# nano.net
KiCad netlist of a schematic drawn in EAGLE
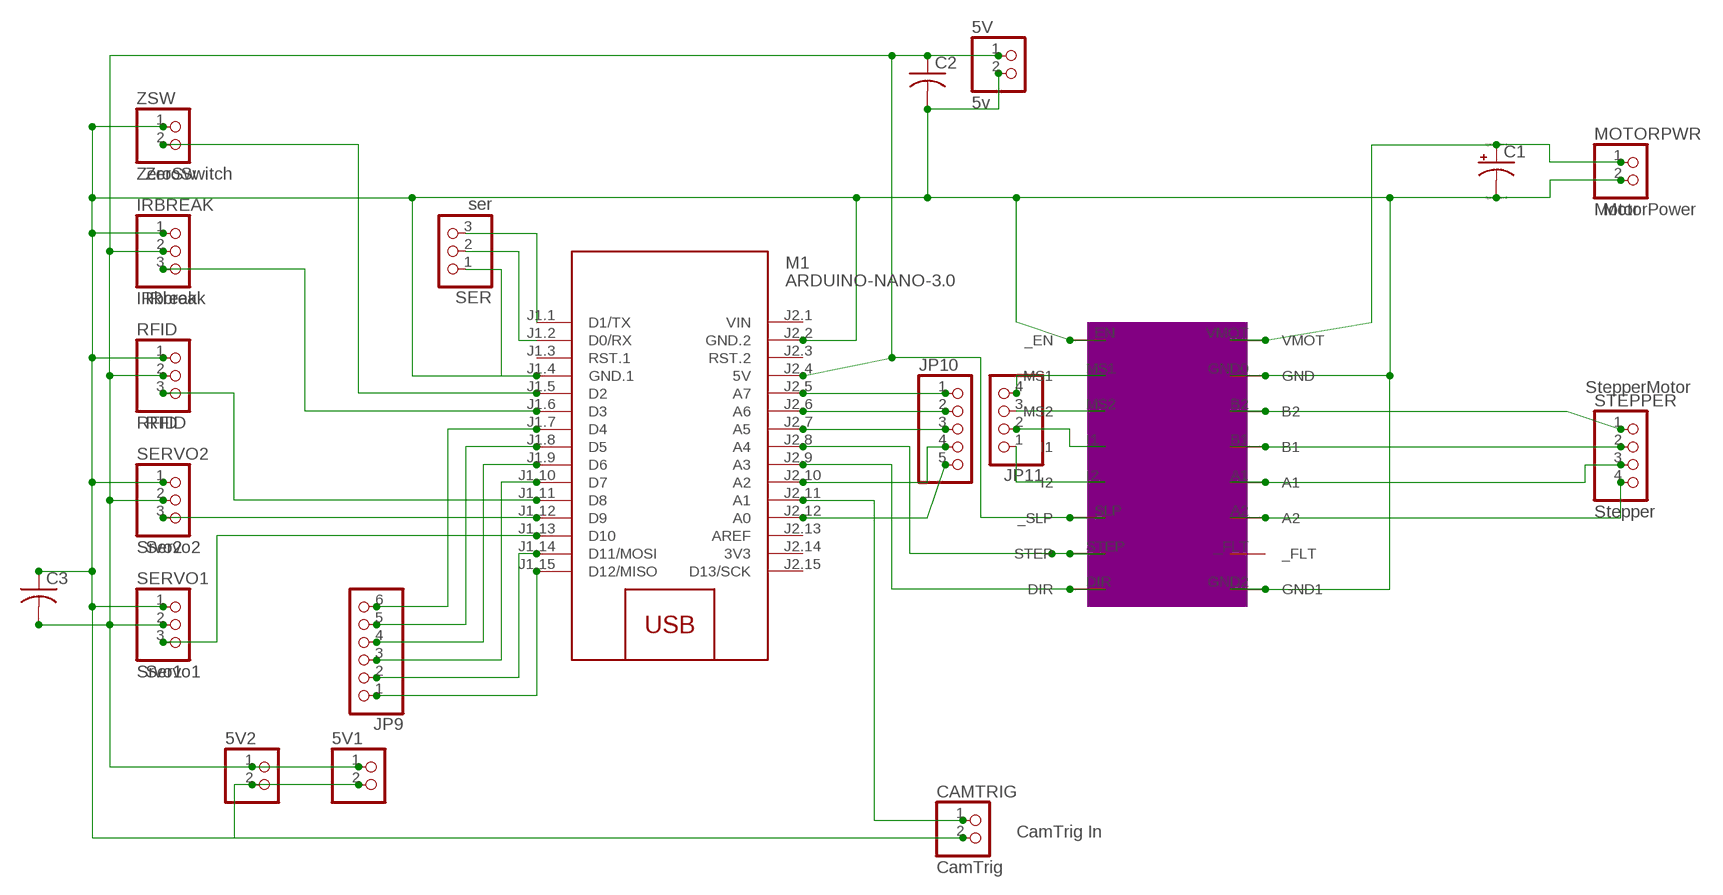
[diagram p0: schematic, sheet 1]

(export (version "E")
  (design (tool "Eeschema 10.0.6"))
  (components
    (comp (ref "5V")
      (value "5v")
      (footprint "eagle-import:1X02")
      (libsource (lib "eagle-import") (part "PINHD-1X2"))
    )
    (comp (ref "5V1")
      (value "PINHD-1X2")
      (footprint "eagle-import:1X02")
      (libsource (lib "eagle-import") (part "PINHD-1X2"))
    )
    (comp (ref "5V2")
      (value "PINHD-1X2")
      (footprint "eagle-import:1X02")
      (libsource (lib "eagle-import") (part "PINHD-1X2"))
    )
    (comp (ref "C1")
      (value "CPOL-USE5-5")
      (footprint "eagle-import:E5-5")
      (libsource (lib "eagle-import") (part "CPOL-USE5-5"))
    )
    (comp (ref "C2")
      (value "C-USC0805")
      (footprint "eagle-import:C0805")
      (libsource (lib "eagle-import") (part "C-USC0805"))
    )
    (comp (ref "C3")
      (value "C-USC0805")
      (footprint "eagle-import:C0805")
      (libsource (lib "eagle-import") (part "C-USC0805"))
    )
    (comp (ref "CAMTRIG")
      (value "CamTrig")
      (footprint "eagle-import:1X02")
      (libsource (lib "eagle-import") (part "PINHD-1X2"))
    )
    (comp (ref "IRBREAK")
      (value "IRbreak")
      (footprint "eagle-import:1X03")
      (libsource (lib "eagle-import") (part "PINHD-1X3"))
    )
    (comp (ref "JP9")
      (value "PINHD-1X6")
      (footprint "eagle-import:1X06")
      (libsource (lib "eagle-import") (part "PINHD-1X6"))
    )
    (comp (ref "JP10")
      (value "PINHD-1X5")
      (footprint "eagle-import:1X05")
      (libsource (lib "eagle-import") (part "PINHD-1X5"))
    )
    (comp (ref "JP11")
      (value "PINHD-1X4")
      (footprint "eagle-import:1X04")
      (libsource (lib "eagle-import") (part "PINHD-1X4"))
    )
    (comp (ref "M1")
      (value "ARDUINO-NANO-3.0")
      (footprint "eagle-import:ARDUINO-NANO-3.0")
      (libsource (lib "eagle-import") (part "ARDUINO-NANO-3.0"))
    )
    (comp (ref "MOTORPWR")
      (value "Motor")
      (footprint "eagle-import:1X02")
      (libsource (lib "eagle-import") (part "PINHD-1X2"))
    )
    (comp (ref "RFID")
      (value "RFID")
      (footprint "eagle-import:1X03")
      (libsource (lib "eagle-import") (part "PINHD-1X3"))
    )
    (comp (ref "SER")
      (value "ser")
      (footprint "eagle-import:1X03")
      (libsource (lib "eagle-import") (part "PINHD-1X3"))
    )
    (comp (ref "SERVO1")
      (value "Srvo1")
      (footprint "eagle-import:1X03")
      (libsource (lib "eagle-import") (part "PINHD-1X3"))
    )
    (comp (ref "SERVO2")
      (value "Srvo2")
      (footprint "eagle-import:1X03")
      (libsource (lib "eagle-import") (part "PINHD-1X3"))
    )
    (comp (ref "STEPPER")
      (value "Stepper")
      (footprint "eagle-import:1X04")
      (libsource (lib "eagle-import") (part "PINHD-1X4"))
    )
    (comp (ref "U$1")
      (value "MP6500")
      (footprint "eagle-import:MP6500")
      (libsource (lib "eagle-import") (part "MP6500"))
    )
    (comp (ref "ZSW")
      (value "ZeroSw")
      (footprint "eagle-import:1X02")
      (libsource (lib "eagle-import") (part "PINHD-1X2"))
    )
  )
  (nets
    (net (code "1") (name "/3V3") (class "Default")
      (node (ref "M1") (pin "J2.14") (pinfunction "3V3_J2.14") (pintype "power_in"))
    )
    (net (code "2") (name "/VIN") (class "Default")
      (node (ref "M1") (pin "J2.1") (pinfunction "VIN_J2.1") (pintype "power_in"))
    )
    (net (code "3") (name "Net-(C1-Pad+)") (class "Default")
      (node (ref "C1") (pin "+") (pinfunction "+_+") (pintype "passive"))
      (node (ref "MOTORPWR") (pin "1") (pinfunction "1_1") (pintype "passive"))
      (node (ref "U$1") (pin "VMOT") (pinfunction "VMOT_VMOT") (pintype "bidirectional"))
    )
    (net (code "4") (name "Net-(JP11-Pad1)") (class "Default")
      (node (ref "JP11") (pin "1") (pinfunction "1_1") (pintype "passive"))
      (node (ref "U$1") (pin "I2") (pinfunction "I2_I2") (pintype "bidirectional"))
    )
    (net (code "5") (name "Net-(JP11-Pad2)") (class "Default")
      (node (ref "JP11") (pin "2") (pinfunction "2_2") (pintype "passive"))
      (node (ref "U$1") (pin "I1") (pinfunction "I1_I1") (pintype "bidirectional"))
    )
    (net (code "6") (name "Net-(JP11-Pad3)") (class "Default")
      (node (ref "JP11") (pin "3") (pinfunction "3_3") (pintype "passive"))
      (node (ref "U$1") (pin "MS2") (pinfunction "MS2_MS2") (pintype "bidirectional"))
    )
    (net (code "7") (name "Net-(JP11-Pad4)") (class "Default")
      (node (ref "JP11") (pin "4") (pinfunction "4_4") (pintype "passive"))
      (node (ref "U$1") (pin "MS1") (pinfunction "MS1_MS1") (pintype "bidirectional"))
    )
    (net (code "8") (name "Net-(M1-5V)") (class "Default")
      (node (ref "5V") (pin "1") (pinfunction "1_1") (pintype "passive"))
      (node (ref "5V1") (pin "1") (pinfunction "1_1") (pintype "passive"))
      (node (ref "5V2") (pin "1") (pinfunction "1_1") (pintype "passive"))
      (node (ref "C2") (pin "1") (pinfunction "1_1") (pintype "passive"))
      (node (ref "C3") (pin "2") (pinfunction "2_2") (pintype "passive"))
      (node (ref "IRBREAK") (pin "2") (pinfunction "2_2") (pintype "passive"))
      (node (ref "M1") (pin "J2.4") (pinfunction "5V_J2.4") (pintype "power_in"))
      (node (ref "RFID") (pin "2") (pinfunction "2_2") (pintype "passive"))
      (node (ref "SERVO1") (pin "2") (pinfunction "2_2") (pintype "passive"))
      (node (ref "SERVO2") (pin "2") (pinfunction "2_2") (pintype "passive"))
      (node (ref "U$1") (pin "_SLP") (pinfunction "_SLP__SLP") (pintype "bidirectional"))
    )
    (net (code "9") (name "Net-(M1-A0)") (class "Default")
      (node (ref "JP10") (pin "5") (pinfunction "5_5") (pintype "passive"))
      (node (ref "M1") (pin "J2.12") (pinfunction "A0_J2.12") (pintype "bidirectional"))
    )
    (net (code "10") (name "Net-(M1-A1)") (class "Default")
      (node (ref "CAMTRIG") (pin "1") (pinfunction "1_1") (pintype "passive"))
      (node (ref "M1") (pin "J2.11") (pinfunction "A1_J2.11") (pintype "bidirectional"))
    )
    (net (code "11") (name "Net-(M1-A2)") (class "Default")
      (node (ref "JP10") (pin "4") (pinfunction "4_4") (pintype "passive"))
      (node (ref "M1") (pin "J2.10") (pinfunction "A2_J2.10") (pintype "bidirectional"))
    )
    (net (code "12") (name "Net-(M1-A3)") (class "Default")
      (node (ref "M1") (pin "J2.9") (pinfunction "A3_J2.9") (pintype "bidirectional"))
      (node (ref "U$1") (pin "DIR") (pinfunction "DIR_DIR") (pintype "bidirectional"))
    )
    (net (code "13") (name "Net-(M1-A4)") (class "Default")
      (node (ref "M1") (pin "J2.8") (pinfunction "A4_J2.8") (pintype "bidirectional"))
      (node (ref "U$1") (pin "STEP") (pinfunction "STEP_STEP") (pintype "bidirectional"))
    )
    (net (code "14") (name "Net-(M1-A5)") (class "Default")
      (node (ref "JP10") (pin "3") (pinfunction "3_3") (pintype "passive"))
      (node (ref "M1") (pin "J2.7") (pinfunction "A5_J2.7") (pintype "bidirectional"))
    )
    (net (code "15") (name "Net-(M1-A6)") (class "Default")
      (node (ref "JP10") (pin "2") (pinfunction "2_2") (pintype "passive"))
      (node (ref "M1") (pin "J2.6") (pinfunction "A6_J2.6") (pintype "bidirectional"))
    )
    (net (code "16") (name "Net-(M1-A7)") (class "Default")
      (node (ref "JP10") (pin "1") (pinfunction "1_1") (pintype "passive"))
      (node (ref "M1") (pin "J2.5") (pinfunction "A7_J2.5") (pintype "bidirectional"))
    )
    (net (code "17") (name "Net-(M1-D0{slash}RX)") (class "Default")
      (node (ref "M1") (pin "J1.2") (pinfunction "D0/RX_J1.2") (pintype "bidirectional"))
      (node (ref "SER") (pin "2") (pinfunction "2_2") (pintype "passive"))
    )
    (net (code "18") (name "Net-(M1-D1{slash}TX)") (class "Default")
      (node (ref "M1") (pin "J1.1") (pinfunction "D1/TX_J1.1") (pintype "bidirectional"))
      (node (ref "SER") (pin "3") (pinfunction "3_3") (pintype "passive"))
    )
    (net (code "19") (name "Net-(M1-D2)") (class "Default")
      (node (ref "M1") (pin "J1.5") (pinfunction "D2_J1.5") (pintype "bidirectional"))
      (node (ref "ZSW") (pin "2") (pinfunction "2_2") (pintype "passive"))
    )
    (net (code "20") (name "Net-(M1-D3)") (class "Default")
      (node (ref "IRBREAK") (pin "3") (pinfunction "3_3") (pintype "passive"))
      (node (ref "M1") (pin "J1.6") (pinfunction "D3_J1.6") (pintype "bidirectional"))
    )
    (net (code "21") (name "Net-(M1-D4)") (class "Default")
      (node (ref "JP9") (pin "6") (pinfunction "6_6") (pintype "passive"))
      (node (ref "M1") (pin "J1.7") (pinfunction "D4_J1.7") (pintype "bidirectional"))
    )
    (net (code "22") (name "Net-(M1-D5)") (class "Default")
      (node (ref "JP9") (pin "5") (pinfunction "5_5") (pintype "passive"))
      (node (ref "M1") (pin "J1.8") (pinfunction "D5_J1.8") (pintype "bidirectional"))
    )
    (net (code "23") (name "Net-(M1-D6)") (class "Default")
      (node (ref "JP9") (pin "4") (pinfunction "4_4") (pintype "passive"))
      (node (ref "M1") (pin "J1.9") (pinfunction "D6_J1.9") (pintype "bidirectional"))
    )
    (net (code "24") (name "Net-(M1-D7)") (class "Default")
      (node (ref "JP9") (pin "3") (pinfunction "3_3") (pintype "passive"))
      (node (ref "M1") (pin "J1.10") (pinfunction "D7_J1.10") (pintype "bidirectional"))
    )
    (net (code "25") (name "Net-(M1-D8)") (class "Default")
      (node (ref "M1") (pin "J1.11") (pinfunction "D8_J1.11") (pintype "bidirectional"))
      (node (ref "RFID") (pin "3") (pinfunction "3_3") (pintype "passive"))
    )
    (net (code "26") (name "Net-(M1-D9)") (class "Default")
      (node (ref "M1") (pin "J1.12") (pinfunction "D9_J1.12") (pintype "bidirectional"))
      (node (ref "SERVO2") (pin "3") (pinfunction "3_3") (pintype "passive"))
    )
    (net (code "27") (name "Net-(M1-D10)") (class "Default")
      (node (ref "M1") (pin "J1.13") (pinfunction "D10_J1.13") (pintype "bidirectional"))
      (node (ref "SERVO1") (pin "3") (pinfunction "3_3") (pintype "passive"))
    )
    (net (code "28") (name "Net-(M1-D11{slash}MOSI)") (class "Default")
      (node (ref "JP9") (pin "2") (pinfunction "2_2") (pintype "passive"))
      (node (ref "M1") (pin "J1.14") (pinfunction "D11/MOSI_J1.14") (pintype "bidirectional"))
    )
    (net (code "29") (name "Net-(M1-D12{slash}MISO)") (class "Default")
      (node (ref "JP9") (pin "1") (pinfunction "1_1") (pintype "passive"))
      (node (ref "M1") (pin "J1.15") (pinfunction "D12/MISO_J1.15") (pintype "bidirectional"))
    )
    (net (code "30") (name "Net-(M1-GND.1)") (class "Default")
      (node (ref "5V") (pin "2") (pinfunction "2_2") (pintype "passive"))
      (node (ref "5V1") (pin "2") (pinfunction "2_2") (pintype "passive"))
      (node (ref "5V2") (pin "2") (pinfunction "2_2") (pintype "passive"))
      (node (ref "C1") (pin "-") (pinfunction "-_-") (pintype "passive"))
      (node (ref "C2") (pin "2") (pinfunction "2_2") (pintype "passive"))
      (node (ref "C3") (pin "1") (pinfunction "1_1") (pintype "passive"))
      (node (ref "CAMTRIG") (pin "2") (pinfunction "2_2") (pintype "passive"))
      (node (ref "IRBREAK") (pin "1") (pinfunction "1_1") (pintype "passive"))
      (node (ref "M1") (pin "J1.4") (pinfunction "GND.1_J1.4") (pintype "power_in"))
      (node (ref "M1") (pin "J2.2") (pinfunction "GND.2_J2.2") (pintype "power_in"))
      (node (ref "MOTORPWR") (pin "2") (pinfunction "2_2") (pintype "passive"))
      (node (ref "RFID") (pin "1") (pinfunction "1_1") (pintype "passive"))
      (node (ref "SER") (pin "1") (pinfunction "1_1") (pintype "passive"))
      (node (ref "SERVO1") (pin "1") (pinfunction "1_1") (pintype "passive"))
      (node (ref "SERVO2") (pin "1") (pinfunction "1_1") (pintype "passive"))
      (node (ref "U$1") (pin "GND0") (pinfunction "GND_GND0") (pintype "bidirectional"))
      (node (ref "U$1") (pin "GND2") (pinfunction "GND1_GND2") (pintype "bidirectional"))
      (node (ref "U$1") (pin "_EN") (pinfunction "_EN__EN") (pintype "bidirectional"))
      (node (ref "ZSW") (pin "1") (pinfunction "1_1") (pintype "passive"))
    )
    (net (code "31") (name "Net-(STEPPER-Pad1)") (class "Default")
      (node (ref "STEPPER") (pin "1") (pinfunction "1_1") (pintype "passive"))
      (node (ref "U$1") (pin "B2") (pinfunction "B2_B2") (pintype "bidirectional"))
    )
    (net (code "32") (name "Net-(STEPPER-Pad2)") (class "Default")
      (node (ref "STEPPER") (pin "2") (pinfunction "2_2") (pintype "passive"))
      (node (ref "U$1") (pin "B1") (pinfunction "B1_B1") (pintype "bidirectional"))
    )
    (net (code "33") (name "Net-(STEPPER-Pad3)") (class "Default")
      (node (ref "STEPPER") (pin "3") (pinfunction "3_3") (pintype "passive"))
      (node (ref "U$1") (pin "A1") (pinfunction "A1_A1") (pintype "bidirectional"))
    )
    (net (code "34") (name "Net-(STEPPER-Pad4)") (class "Default")
      (node (ref "STEPPER") (pin "4") (pinfunction "4_4") (pintype "passive"))
      (node (ref "U$1") (pin "A2") (pinfunction "A2_A2") (pintype "bidirectional"))
    )
    (net (code "35") (name "unconnected-(M1-AREF-PadJ2.13)") (class "Default")
      (node (ref "M1") (pin "J2.13") (pinfunction "AREF_J2.13") (pintype "bidirectional"))
    )
    (net (code "36") (name "unconnected-(M1-D13{slash}SCK-PadJ2.15)") (class "Default")
      (node (ref "M1") (pin "J2.15") (pinfunction "D13/SCK_J2.15") (pintype "bidirectional"))
    )
    (net (code "37") (name "unconnected-(M1-RST.1-PadJ1.3)") (class "Default")
      (node (ref "M1") (pin "J1.3") (pinfunction "RST.1_J1.3") (pintype "bidirectional"))
    )
    (net (code "38") (name "unconnected-(M1-RST.2-PadJ2.3)") (class "Default")
      (node (ref "M1") (pin "J2.3") (pinfunction "RST.2_J2.3") (pintype "bidirectional"))
    )
    (net (code "39") (name "unconnected-(U$1-Pad_FLT)") (class "Default")
      (node (ref "U$1") (pin "_FLT") (pinfunction "_FLT__FLT") (pintype "bidirectional"))
    )
  )
)
